# modem_breakout.net
KiCad netlist of a schematic drawn in EAGLE
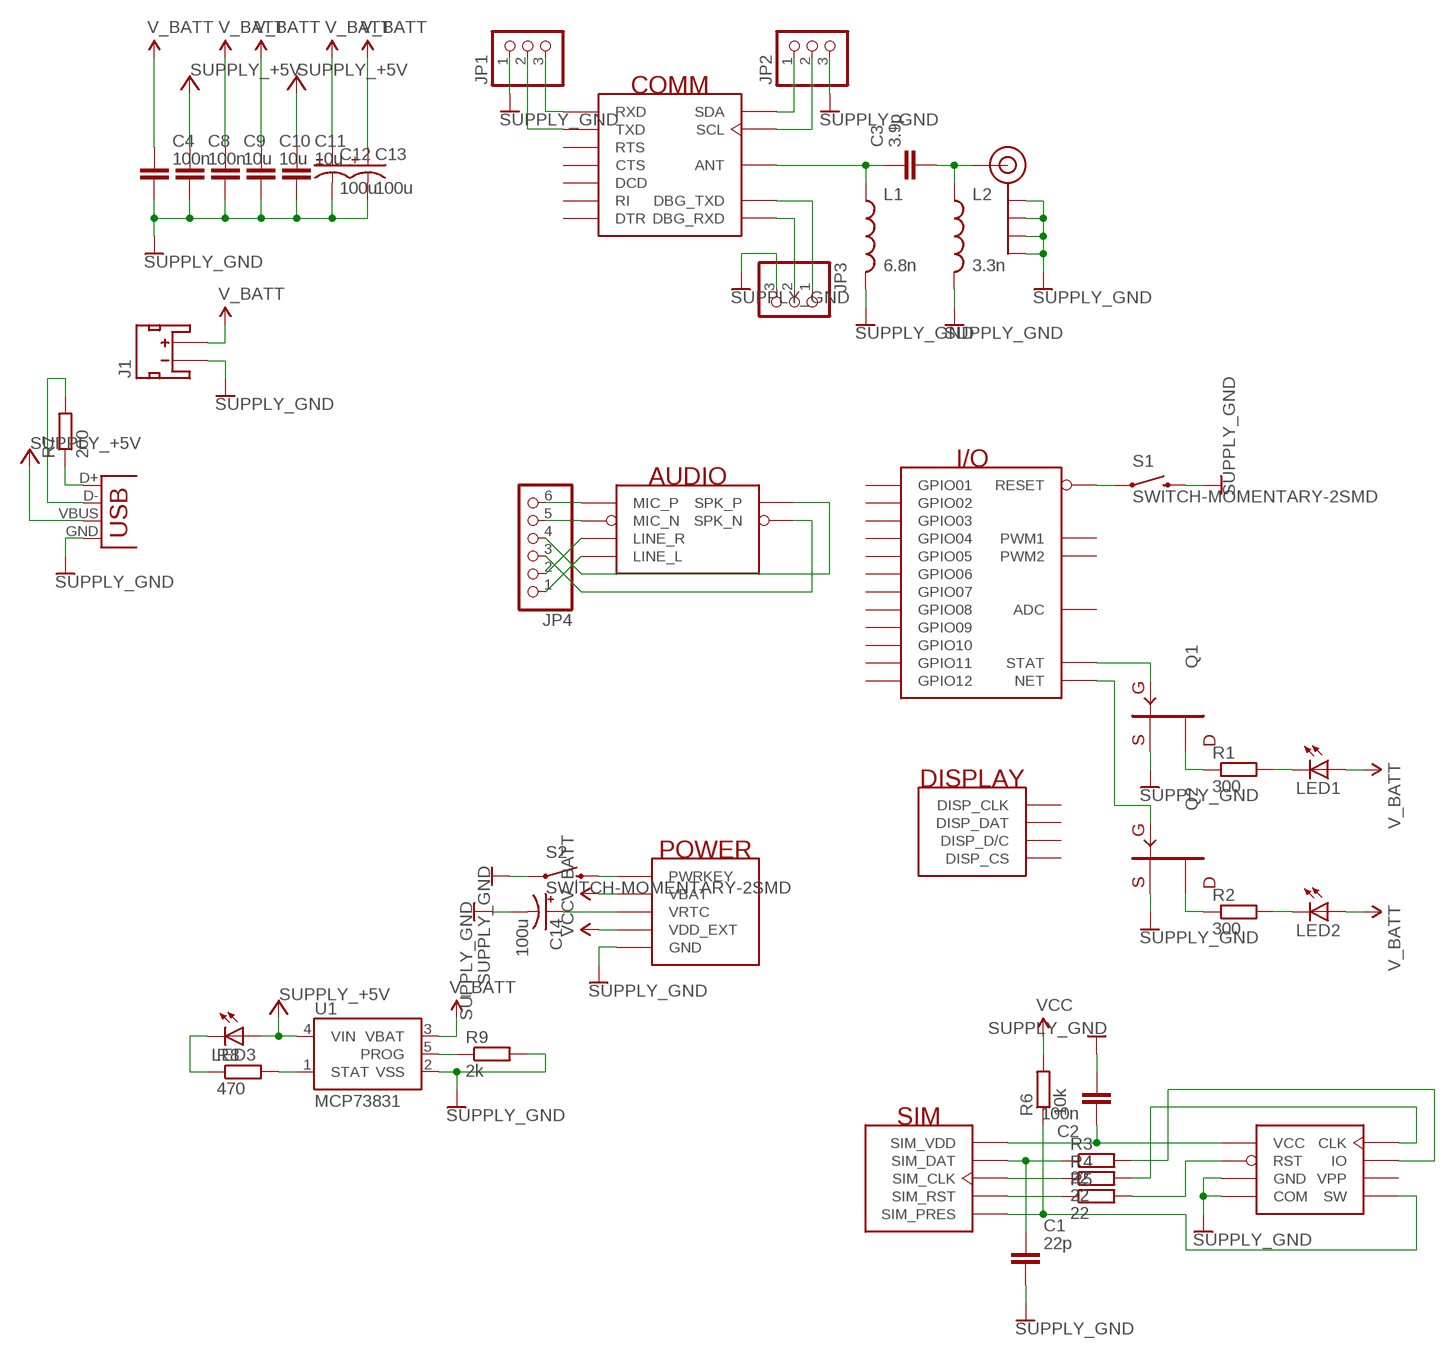
[diagram p0: schematic, sheet 1]

(export (version "E")
  (design (tool "Eeschema 10.0.6"))
  (components
    (comp (ref "C1")
      (value "22p")
      (footprint "eagle-import:C402")
      (libsource (lib "eagle-import") (part "CAPACITOR_NPOL-0402"))
    )
    (comp (ref "C2")
      (value "100n")
      (footprint "eagle-import:C402")
      (libsource (lib "eagle-import") (part "CAPACITOR_NPOL-0402"))
    )
    (comp (ref "C3")
      (value "3.9p")
      (footprint "eagle-import:C603")
      (libsource (lib "eagle-import") (part "CAPACITOR_NPOL-0603"))
    )
    (comp (ref "C4")
      (value "100n")
      (footprint "eagle-import:C402")
      (libsource (lib "eagle-import") (part "CAPACITOR_NPOL-0402"))
    )
    (comp (ref "C8")
      (value "100n")
      (footprint "eagle-import:C402")
      (libsource (lib "eagle-import") (part "CAPACITOR_NPOL-0402"))
    )
    (comp (ref "C9")
      (value "10u")
      (footprint "eagle-import:C805")
      (libsource (lib "eagle-import") (part "CAPACITOR_NPOL-0805"))
    )
    (comp (ref "C10")
      (value "10u")
      (footprint "eagle-import:C805")
      (libsource (lib "eagle-import") (part "CAPACITOR_NPOL-0805"))
    )
    (comp (ref "C11")
      (value "10u")
      (footprint "eagle-import:C805")
      (libsource (lib "eagle-import") (part "CAPACITOR_NPOL-0805"))
    )
    (comp (ref "C12")
      (value "100u")
      (footprint "eagle-import:EIA3528")
      (libsource (lib "eagle-import") (part "CAP_POL3528"))
    )
    (comp (ref "C13")
      (value "100u")
      (footprint "eagle-import:EIA3528")
      (libsource (lib "eagle-import") (part "CAP_POL3528"))
    )
    (comp (ref "C14")
      (value "100u")
      (footprint "eagle-import:EIA3528")
      (libsource (lib "eagle-import") (part "CAP_POL3528"))
    )
    (comp (ref "J$1")
      (value "SMA_EDGE")
      (footprint "eagle-import:SMA-EDGE")
      (libsource (lib "eagle-import") (part "SMA_EDGE"))
    )
    (comp (ref "J1")
      (value "JST_2MM_MALE")
      (footprint "eagle-import:JST-2-SMD")
      (libsource (lib "eagle-import") (part "JST_2MM_MALE"))
    )
    (comp (ref "JP1")
      (value "PINHD-1X3")
      (footprint "eagle-import:1X03")
      (libsource (lib "eagle-import") (part "PINHD-1X3"))
    )
    (comp (ref "JP2")
      (value "PINHD-1X3")
      (footprint "eagle-import:1X03")
      (libsource (lib "eagle-import") (part "PINHD-1X3"))
    )
    (comp (ref "JP3")
      (value "PINHD-1X3")
      (footprint "eagle-import:1X03")
      (libsource (lib "eagle-import") (part "PINHD-1X3"))
    )
    (comp (ref "JP4")
      (value "PINHD-1X6")
      (footprint "eagle-import:1X06")
      (libsource (lib "eagle-import") (part "PINHD-1X6"))
    )
    (comp (ref "JP5")
      (value "USB-SMD-NS")
      (footprint "eagle-import:USB-MINIB-NOSTOP")
      (libsource (lib "eagle-import") (part "USB-SMD-NS"))
    )
    (comp (ref "L1")
      (value "6.8n")
      (footprint "eagle-import:0603")
      (libsource (lib "eagle-import") (part "INDUCTOR0603"))
    )
    (comp (ref "L2")
      (value "3.3n")
      (footprint "eagle-import:0603")
      (libsource (lib "eagle-import") (part "INDUCTOR0603"))
    )
    (comp (ref "LED1")
      (value "LED-0603")
      (footprint "eagle-import:LED-603")
      (libsource (lib "eagle-import") (part "LED-0603"))
    )
    (comp (ref "LED2")
      (value "LED-0603")
      (footprint "eagle-import:LED-603")
      (libsource (lib "eagle-import") (part "LED-0603"))
    )
    (comp (ref "LED3")
      (value "LED-0603")
      (footprint "eagle-import:LED-603")
      (libsource (lib "eagle-import") (part "LED-0603"))
    )
    (comp (ref "Q1")
      (value "TRANSISTOR_FET-N")
      (footprint "eagle-import:SOT-23")
      (libsource (lib "eagle-import") (part "TRANSISTOR_FET-N"))
    )
    (comp (ref "Q2")
      (value "TRANSISTOR_FET-N")
      (footprint "eagle-import:SOT-23")
      (libsource (lib "eagle-import") (part "TRANSISTOR_FET-N"))
    )
    (comp (ref "R1")
      (value "300")
      (footprint "eagle-import:R603")
      (libsource (lib "eagle-import") (part "RESISTOR-0603"))
    )
    (comp (ref "R2")
      (value "300")
      (footprint "eagle-import:R603")
      (libsource (lib "eagle-import") (part "RESISTOR-0603"))
    )
    (comp (ref "R3")
      (value "22")
      (footprint "eagle-import:R402")
      (libsource (lib "eagle-import") (part "RESISTOR-0402"))
    )
    (comp (ref "R4")
      (value "22")
      (footprint "eagle-import:R402")
      (libsource (lib "eagle-import") (part "RESISTOR-0402"))
    )
    (comp (ref "R5")
      (value "22")
      (footprint "eagle-import:R402")
      (libsource (lib "eagle-import") (part "RESISTOR-0402"))
    )
    (comp (ref "R6")
      (value "10k")
      (footprint "eagle-import:R402")
      (libsource (lib "eagle-import") (part "RESISTOR-0402"))
    )
    (comp (ref "R7")
      (value "200")
      (footprint "eagle-import:R603")
      (libsource (lib "eagle-import") (part "RESISTOR-0603"))
    )
    (comp (ref "R8")
      (value "470")
      (footprint "eagle-import:R603")
      (libsource (lib "eagle-import") (part "RESISTOR-0603"))
    )
    (comp (ref "R9")
      (value "2k")
      (footprint "eagle-import:R402")
      (libsource (lib "eagle-import") (part "RESISTOR-0402"))
    )
    (comp (ref "S1")
      (value "SWITCH-MOMENTARY-2SMD")
      (footprint "eagle-import:TACTILE_SWITCH_SMD")
      (libsource (lib "eagle-import") (part "SWITCH-MOMENTARY-2SMD"))
    )
    (comp (ref "S2")
      (value "SWITCH-MOMENTARY-2SMD")
      (footprint "eagle-import:TACTILE_SWITCH_SMD")
      (libsource (lib "eagle-import") (part "SWITCH-MOMENTARY-2SMD"))
    )
    (comp (ref "U$1")
      (value "SIM900")
      (footprint "eagle-import:SIM900")
      (libsource (lib "eagle-import") (part "SIM900"))
    )
    (comp (ref "U$2")
      (value "SIM-MICRO")
      (footprint "eagle-import:1041180811")
      (libsource (lib "eagle-import") (part "SIM-MICRO"))
    )
    (comp (ref "U1")
      (value "MCP73831")
      (footprint "eagle-import:SOT23-5")
      (libsource (lib "eagle-import") (part "MCP73831"))
    )
  )
  (nets
    (net (code "1") (name "Net-(C14-+)") (class "Default")
      (node (ref "C14") (pin "A") (pinfunction "+_A") (pintype "passive"))
      (node (ref "U$1") (pin "P$26") (pinfunction "VRTC_P$26") (pintype "power_in"))
    )
    (net (code "2") (name "Net-(J$1-SIGNAL)") (class "Default")
      (node (ref "C3") (pin "2") (pinfunction "2_2") (pintype "passive"))
      (node (ref "J$1") (pin "SIG") (pinfunction "SIGNAL_SIG") (pintype "bidirectional"))
      (node (ref "L2") (pin "1") (pinfunction "1_1") (pintype "passive"))
    )
    (net (code "3") (name "Net-(JP5-PadD+)") (class "Default")
      (node (ref "JP5") (pin "D+") (pinfunction "D+_D+") (pintype "bidirectional"))
      (node (ref "R7") (pin "1") (pinfunction "1_1") (pintype "passive"))
    )
    (net (code "4") (name "Net-(JP5-PadD-)") (class "Default")
      (node (ref "JP5") (pin "D-") (pinfunction "D-_D-") (pintype "bidirectional"))
      (node (ref "R7") (pin "2") (pinfunction "2_2") (pintype "passive"))
    )
    (net (code "5") (name "Net-(LED1-PadC)") (class "Default")
      (node (ref "LED1") (pin "C") (pinfunction "C_C") (pintype "passive"))
      (node (ref "R1") (pin "2") (pinfunction "2_2") (pintype "passive"))
    )
    (net (code "6") (name "Net-(LED2-PadC)") (class "Default")
      (node (ref "LED2") (pin "C") (pinfunction "C_C") (pintype "passive"))
      (node (ref "R2") (pin "2") (pinfunction "2_2") (pintype "passive"))
    )
    (net (code "7") (name "Net-(LED3-PadC)") (class "Default")
      (node (ref "LED3") (pin "C") (pinfunction "C_C") (pintype "passive"))
      (node (ref "R8") (pin "1") (pinfunction "1_1") (pintype "passive"))
    )
    (net (code "8") (name "Net-(Q1-D)") (class "Default")
      (node (ref "Q1") (pin "3") (pinfunction "D_3") (pintype "bidirectional"))
      (node (ref "R1") (pin "1") (pinfunction "1_1") (pintype "passive"))
    )
    (net (code "9") (name "Net-(Q1-G)") (class "Default")
      (node (ref "Q1") (pin "1") (pinfunction "G_1") (pintype "bidirectional"))
      (node (ref "U$1") (pin "P$66") (pinfunction "STAT_P$66") (pintype "output"))
    )
    (net (code "10") (name "Net-(Q2-D)") (class "Default")
      (node (ref "Q2") (pin "3") (pinfunction "D_3") (pintype "bidirectional"))
      (node (ref "R2") (pin "1") (pinfunction "1_1") (pintype "passive"))
    )
    (net (code "11") (name "Net-(Q2-G)") (class "Default")
      (node (ref "Q2") (pin "1") (pinfunction "G_1") (pintype "bidirectional"))
      (node (ref "U$1") (pin "P$52") (pinfunction "NET_P$52") (pintype "output"))
    )
    (net (code "12") (name "Net-(S2-2)") (class "Default")
      (node (ref "S2") (pin "3") (pinfunction "2_3") (pintype "passive"))
      (node (ref "U$1") (pin "P$1") (pinfunction "PWRKEY_P$1") (pintype "input"))
    )
    (net (code "13") (name "Net-(U$1A-LINE_L)") (class "Default")
      (node (ref "JP4") (pin "1") (pinfunction "1_1") (pintype "passive"))
      (node (ref "U$1") (pin "P$24") (pinfunction "LINE_L_P$24") (pintype "input"))
    )
    (net (code "14") (name "Net-(U$1A-LINE_R)") (class "Default")
      (node (ref "JP4") (pin "2") (pinfunction "2_2") (pintype "passive"))
      (node (ref "U$1") (pin "P$23") (pinfunction "LINE_R_P$23") (pintype "input"))
    )
    (net (code "15") (name "Net-(U$1A-MIC_N)") (class "Default")
      (node (ref "JP4") (pin "5") (pinfunction "5_5") (pintype "passive"))
      (node (ref "U$1") (pin "P$20") (pinfunction "MIC_N_P$20") (pintype "input"))
    )
    (net (code "16") (name "Net-(U$1A-MIC_P)") (class "Default")
      (node (ref "JP4") (pin "6") (pinfunction "6_6") (pintype "passive"))
      (node (ref "U$1") (pin "P$19") (pinfunction "MIC_P_P$19") (pintype "input"))
    )
    (net (code "17") (name "Net-(U$1A-SPK_N)") (class "Default")
      (node (ref "JP4") (pin "3") (pinfunction "3_3") (pintype "passive"))
      (node (ref "U$1") (pin "P$22") (pinfunction "SPK_N_P$22") (pintype "output"))
    )
    (net (code "18") (name "Net-(U$1A-SPK_P)") (class "Default")
      (node (ref "JP4") (pin "4") (pinfunction "4_4") (pintype "passive"))
      (node (ref "U$1") (pin "P$21") (pinfunction "SPK_P_P$21") (pintype "output"))
    )
    (net (code "19") (name "Net-(U$1B-ANT)") (class "Default")
      (node (ref "C3") (pin "1") (pinfunction "1_1") (pintype "passive"))
      (node (ref "L1") (pin "1") (pinfunction "1_1") (pintype "passive"))
      (node (ref "U$1") (pin "P$60") (pinfunction "ANT_P$60") (pintype "bidirectional"))
    )
    (net (code "20") (name "Net-(U$1B-DBG_RXD)") (class "Default")
      (node (ref "JP3") (pin "2") (pinfunction "2_2") (pintype "passive"))
      (node (ref "U$1") (pin "P$28") (pinfunction "DBG_RXD_P$28") (pintype "input"))
    )
    (net (code "21") (name "Net-(U$1B-DBG_TXD)") (class "Default")
      (node (ref "JP3") (pin "1") (pinfunction "1_1") (pintype "passive"))
      (node (ref "U$1") (pin "P$27") (pinfunction "DBG_TXD_P$27") (pintype "output"))
    )
    (net (code "22") (name "Net-(U$1B-RXD)") (class "Default")
      (node (ref "JP1") (pin "3") (pinfunction "3_3") (pintype "passive"))
      (node (ref "U$1") (pin "P$10") (pinfunction "RXD_P$10") (pintype "input"))
    )
    (net (code "23") (name "Net-(U$1B-SCL)") (class "Default")
      (node (ref "JP2") (pin "2") (pinfunction "2_2") (pintype "passive"))
      (node (ref "U$1") (pin "P$38") (pinfunction "SCL_P$38") (pintype "bidirectional"))
    )
    (net (code "24") (name "Net-(U$1B-SDA)") (class "Default")
      (node (ref "JP2") (pin "1") (pinfunction "1_1") (pintype "passive"))
      (node (ref "U$1") (pin "P$37") (pinfunction "SDA_P$37") (pintype "output"))
    )
    (net (code "25") (name "Net-(U$1B-TXD)") (class "Default")
      (node (ref "JP1") (pin "2") (pinfunction "2_2") (pintype "passive"))
      (node (ref "U$1") (pin "P$9") (pinfunction "TXD_P$9") (pintype "output"))
    )
    (net (code "26") (name "Net-(U$1C-RESET)") (class "Default")
      (node (ref "S1") (pin "1") (pinfunction "1_1") (pintype "passive"))
      (node (ref "U$1") (pin "P$16") (pinfunction "RESET_P$16") (pintype "input"))
    )
    (net (code "27") (name "Net-(U$1F-SIM_CLK)") (class "Default")
      (node (ref "R4") (pin "1") (pinfunction "1_1") (pintype "passive"))
      (node (ref "U$1") (pin "P$32") (pinfunction "SIM_CLK_P$32") (pintype "output"))
    )
    (net (code "28") (name "Net-(U$1F-SIM_DAT)") (class "Default")
      (node (ref "C1") (pin "1") (pinfunction "1_1") (pintype "passive"))
      (node (ref "R3") (pin "1") (pinfunction "1_1") (pintype "passive"))
      (node (ref "U$1") (pin "P$31") (pinfunction "SIM_DAT_P$31") (pintype "bidirectional"))
    )
    (net (code "29") (name "Net-(U$1F-SIM_PRES)") (class "Default")
      (node (ref "R6") (pin "1") (pinfunction "1_1") (pintype "passive"))
      (node (ref "U$1") (pin "P$34") (pinfunction "SIM_PRES_P$34") (pintype "input"))
      (node (ref "U$2") (pin "DETECT") (pinfunction "SW_DETECT") (pintype "bidirectional"))
    )
    (net (code "30") (name "Net-(U$1F-SIM_RST)") (class "Default")
      (node (ref "R5") (pin "1") (pinfunction "1_1") (pintype "passive"))
      (node (ref "U$1") (pin "P$33") (pinfunction "SIM_RST_P$33") (pintype "output"))
    )
    (net (code "31") (name "Net-(U$1F-SIM_VDD)") (class "Default")
      (node (ref "C2") (pin "1") (pinfunction "1_1") (pintype "passive"))
      (node (ref "U$1") (pin "P$30") (pinfunction "SIM_VDD_P$30") (pintype "power_in"))
      (node (ref "U$2") (pin "1") (pinfunction "VCC_1") (pintype "power_in"))
    )
    (net (code "32") (name "Net-(U$2-CLK)") (class "Default")
      (node (ref "R4") (pin "2") (pinfunction "2_2") (pintype "passive"))
      (node (ref "U$2") (pin "3") (pinfunction "CLK_3") (pintype "input"))
    )
    (net (code "33") (name "Net-(U$2-IO)") (class "Default")
      (node (ref "R3") (pin "2") (pinfunction "2_2") (pintype "passive"))
      (node (ref "U$2") (pin "7") (pinfunction "IO_7") (pintype "bidirectional"))
    )
    (net (code "34") (name "Net-(U$2-RST)") (class "Default")
      (node (ref "R5") (pin "2") (pinfunction "2_2") (pintype "passive"))
      (node (ref "U$2") (pin "2") (pinfunction "RST_2") (pintype "input"))
    )
    (net (code "35") (name "Net-(U1-PROG)") (class "Default")
      (node (ref "R9") (pin "1") (pinfunction "1_1") (pintype "passive"))
      (node (ref "U1") (pin "5") (pinfunction "PROG_5") (pintype "input"))
    )
    (net (code "36") (name "Net-(U1-STAT)") (class "Default")
      (node (ref "R8") (pin "2") (pinfunction "2_2") (pintype "passive"))
      (node (ref "U1") (pin "1") (pinfunction "STAT_1") (pintype "output"))
    )
    (net (code "37") (name "SUPPLY_+5V") (class "Default")
      (node (ref "C11") (pin "1") (pinfunction "1_1") (pintype "passive"))
      (node (ref "C8") (pin "1") (pinfunction "1_1") (pintype "passive"))
      (node (ref "JP5") (pin "VBUS") (pinfunction "VBUS_VBUS") (pintype "bidirectional"))
      (node (ref "LED3") (pin "A") (pinfunction "A_A") (pintype "passive"))
      (node (ref "U1") (pin "4") (pinfunction "VIN_4") (pintype "power_in"))
    )
    (net (code "38") (name "SUPPLY_GND") (class "Default")
      (node (ref "C1") (pin "2") (pinfunction "2_2") (pintype "passive"))
      (node (ref "C10") (pin "2") (pinfunction "2_2") (pintype "passive"))
      (node (ref "C11") (pin "2") (pinfunction "2_2") (pintype "passive"))
      (node (ref "C12") (pin "C") (pinfunction "-_C") (pintype "passive"))
      (node (ref "C13") (pin "C") (pinfunction "-_C") (pintype "passive"))
      (node (ref "C14") (pin "C") (pinfunction "-_C") (pintype "passive"))
      (node (ref "C2") (pin "2") (pinfunction "2_2") (pintype "passive"))
      (node (ref "C4") (pin "2") (pinfunction "2_2") (pintype "passive"))
      (node (ref "C8") (pin "2") (pinfunction "2_2") (pintype "passive"))
      (node (ref "C9") (pin "2") (pinfunction "2_2") (pintype "passive"))
      (node (ref "J$1") (pin "GND@0") (pinfunction "GND_GND@0") (pintype "bidirectional"))
      (node (ref "J$1") (pin "GND@1") (pinfunction "GND_GND@1") (pintype "bidirectional"))
      (node (ref "J$1") (pin "GND@2") (pinfunction "GND_GND@2") (pintype "bidirectional"))
      (node (ref "J$1") (pin "GND@3") (pinfunction "GND_GND@3") (pintype "bidirectional"))
      (node (ref "J1") (pin "1") (pinfunction "-_1") (pintype "bidirectional"))
      (node (ref "JP1") (pin "1") (pinfunction "1_1") (pintype "passive"))
      (node (ref "JP2") (pin "3") (pinfunction "3_3") (pintype "passive"))
      (node (ref "JP3") (pin "3") (pinfunction "3_3") (pintype "passive"))
      (node (ref "JP5") (pin "GND") (pinfunction "GND_GND") (pintype "bidirectional"))
      (node (ref "L1") (pin "2") (pinfunction "2_2") (pintype "passive"))
      (node (ref "L2") (pin "2") (pinfunction "2_2") (pintype "passive"))
      (node (ref "Q1") (pin "2") (pinfunction "S_2") (pintype "bidirectional"))
      (node (ref "Q2") (pin "2") (pinfunction "S_2") (pintype "bidirectional"))
      (node (ref "R9") (pin "2") (pinfunction "2_2") (pintype "passive"))
      (node (ref "S1") (pin "3") (pinfunction "2_3") (pintype "passive"))
      (node (ref "S2") (pin "1") (pinfunction "1_1") (pintype "passive"))
      (node (ref "U$1") (pin "P$17") (pinfunction "GND_P$17") (pintype "power_in"))
      (node (ref "U$1") (pin "P$18") (pinfunction "GND_P$18") (pintype "power_in"))
      (node (ref "U$1") (pin "P$29") (pinfunction "GND_P$29") (pintype "power_in"))
      (node (ref "U$1") (pin "P$39") (pinfunction "GND_P$39") (pintype "power_in"))
      (node (ref "U$1") (pin "P$45") (pinfunction "GND_P$45") (pintype "power_in"))
      (node (ref "U$1") (pin "P$46") (pinfunction "GND_P$46") (pintype "power_in"))
      (node (ref "U$1") (pin "P$53") (pinfunction "GND_P$53") (pintype "power_in"))
      (node (ref "U$1") (pin "P$54") (pinfunction "GND_P$54") (pintype "power_in"))
      (node (ref "U$1") (pin "P$58") (pinfunction "GND_P$58") (pintype "power_in"))
      (node (ref "U$1") (pin "P$59") (pinfunction "GND_P$59") (pintype "power_in"))
      (node (ref "U$1") (pin "P$61") (pinfunction "GND_P$61") (pintype "power_in"))
      (node (ref "U$1") (pin "P$62") (pinfunction "GND_P$62") (pintype "power_in"))
      (node (ref "U$1") (pin "P$63") (pinfunction "GND_P$63") (pintype "power_in"))
      (node (ref "U$1") (pin "P$64") (pinfunction "GND_P$64") (pintype "power_in"))
      (node (ref "U$1") (pin "P$65") (pinfunction "GND_P$65") (pintype "power_in"))
      (node (ref "U$2") (pin "5") (pinfunction "GND_5") (pintype "power_in"))
      (node (ref "U$2") (pin "COMMON") (pinfunction "COM_COMMON") (pintype "bidirectional"))
      (node (ref "U$2") (pin "G1") (pinfunction "GND_G1") (pintype "power_in"))
      (node (ref "U$2") (pin "G2") (pinfunction "GND_G2") (pintype "power_in"))
      (node (ref "U$2") (pin "G3") (pinfunction "GND_G3") (pintype "power_in"))
      (node (ref "U$2") (pin "G4") (pinfunction "GND_G4") (pintype "power_in"))
      (node (ref "U$2") (pin "G5") (pinfunction "GND_G5") (pintype "power_in"))
      (node (ref "U$2") (pin "G6") (pinfunction "GND_G6") (pintype "power_in"))
      (node (ref "U1") (pin "2") (pinfunction "VSS_2") (pintype "power_in"))
    )
    (net (code "39") (name "VCC") (class "Default")
      (node (ref "R6") (pin "2") (pinfunction "2_2") (pintype "passive"))
      (node (ref "U$1") (pin "P$15") (pinfunction "VDD_EXT_P$15") (pintype "power_in"))
    )
    (net (code "40") (name "V_BATT") (class "Default")
      (node (ref "C10") (pin "1") (pinfunction "1_1") (pintype "passive"))
      (node (ref "C12") (pin "A") (pinfunction "+_A") (pintype "passive"))
      (node (ref "C13") (pin "A") (pinfunction "+_A") (pintype "passive"))
      (node (ref "C4") (pin "1") (pinfunction "1_1") (pintype "passive"))
      (node (ref "C9") (pin "1") (pinfunction "1_1") (pintype "passive"))
      (node (ref "J1") (pin "2") (pinfunction "+_2") (pintype "bidirectional"))
      (node (ref "LED1") (pin "A") (pinfunction "A_A") (pintype "passive"))
      (node (ref "LED2") (pin "A") (pinfunction "A_A") (pintype "passive"))
      (node (ref "U$1") (pin "P$55") (pinfunction "VBAT_P$55") (pintype "power_in"))
      (node (ref "U$1") (pin "P$56") (pinfunction "VBAT_P$56") (pintype "power_in"))
      (node (ref "U$1") (pin "P$57") (pinfunction "VBAT_P$57") (pintype "power_in"))
      (node (ref "U1") (pin "3") (pinfunction "VBAT_3") (pintype "power_in"))
    )
    (net (code "41") (name "unconnected-(J1-PAD1-PadNC1)") (class "Default")
      (node (ref "J1") (pin "NC1") (pinfunction "PAD1_NC1") (pintype "bidirectional"))
    )
    (net (code "42") (name "unconnected-(J1-PAD2-PadNC2)") (class "Default")
      (node (ref "J1") (pin "NC2") (pinfunction "PAD2_NC2") (pintype "bidirectional"))
    )
    (net (code "43") (name "unconnected-(U$1B-CTS-PadP$7)") (class "Default")
      (node (ref "U$1") (pin "P$7") (pinfunction "CTS_P$7") (pintype "output"))
    )
    (net (code "44") (name "unconnected-(U$1B-DCD-PadP$5)") (class "Default")
      (node (ref "U$1") (pin "P$5") (pinfunction "DCD_P$5") (pintype "output"))
    )
    (net (code "45") (name "unconnected-(U$1B-DTR-PadP$3)") (class "Default")
      (node (ref "U$1") (pin "P$3") (pinfunction "DTR_P$3") (pintype "input"))
    )
    (net (code "46") (name "unconnected-(U$1B-RI-PadP$4)") (class "Default")
      (node (ref "U$1") (pin "P$4") (pinfunction "RI_P$4") (pintype "output"))
    )
    (net (code "47") (name "unconnected-(U$1B-RTS-PadP$8)") (class "Default")
      (node (ref "U$1") (pin "P$8") (pinfunction "RTS_P$8") (pintype "input"))
    )
    (net (code "48") (name "unconnected-(U$1C-ADC-PadP$25)") (class "Default")
      (node (ref "U$1") (pin "P$25") (pinfunction "ADC_P$25") (pintype "input"))
    )
    (net (code "49") (name "unconnected-(U$1C-GPIO01-PadP$40)") (class "Default")
      (node (ref "U$1") (pin "P$40") (pinfunction "GPIO01_P$40") (pintype "bidirectional"))
    )
    (net (code "50") (name "unconnected-(U$1C-GPIO02-PadP$41)") (class "Default")
      (node (ref "U$1") (pin "P$41") (pinfunction "GPIO02_P$41") (pintype "bidirectional"))
    )
    (net (code "51") (name "unconnected-(U$1C-GPIO03-PadP$42)") (class "Default")
      (node (ref "U$1") (pin "P$42") (pinfunction "GPIO03_P$42") (pintype "bidirectional"))
    )
    (net (code "52") (name "unconnected-(U$1C-GPIO04-PadP$43)") (class "Default")
      (node (ref "U$1") (pin "P$43") (pinfunction "GPIO04_P$43") (pintype "bidirectional"))
    )
    (net (code "53") (name "unconnected-(U$1C-GPIO05-PadP$44)") (class "Default")
      (node (ref "U$1") (pin "P$44") (pinfunction "GPIO05_P$44") (pintype "bidirectional"))
    )
    (net (code "54") (name "unconnected-(U$1C-GPIO06-PadP$47)") (class "Default")
      (node (ref "U$1") (pin "P$47") (pinfunction "GPIO06_P$47") (pintype "bidirectional"))
    )
    (net (code "55") (name "unconnected-(U$1C-GPIO07-PadP$48)") (class "Default")
      (node (ref "U$1") (pin "P$48") (pinfunction "GPIO07_P$48") (pintype "bidirectional"))
    )
    (net (code "56") (name "unconnected-(U$1C-GPIO08-PadP$49)") (class "Default")
      (node (ref "U$1") (pin "P$49") (pinfunction "GPIO08_P$49") (pintype "bidirectional"))
    )
    (net (code "57") (name "unconnected-(U$1C-GPIO09-PadP$50)") (class "Default")
      (node (ref "U$1") (pin "P$50") (pinfunction "GPIO09_P$50") (pintype "bidirectional"))
    )
    (net (code "58") (name "unconnected-(U$1C-GPIO10-PadP$51)") (class "Default")
      (node (ref "U$1") (pin "P$51") (pinfunction "GPIO10_P$51") (pintype "bidirectional"))
    )
    (net (code "59") (name "unconnected-(U$1C-GPIO11-PadP$67)") (class "Default")
      (node (ref "U$1") (pin "P$67") (pinfunction "GPIO11_P$67") (pintype "bidirectional"))
    )
    (net (code "60") (name "unconnected-(U$1C-GPIO12-PadP$68)") (class "Default")
      (node (ref "U$1") (pin "P$68") (pinfunction "GPIO12_P$68") (pintype "bidirectional"))
    )
    (net (code "61") (name "unconnected-(U$1C-PWM1-PadP$35)") (class "Default")
      (node (ref "U$1") (pin "P$35") (pinfunction "PWM1_P$35") (pintype "output"))
    )
    (net (code "62") (name "unconnected-(U$1C-PWM2-PadP$36)") (class "Default")
      (node (ref "U$1") (pin "P$36") (pinfunction "PWM2_P$36") (pintype "output"))
    )
    (net (code "63") (name "unconnected-(U$1D-DISP_CLK-PadP$11)") (class "Default")
      (node (ref "U$1") (pin "P$11") (pinfunction "DISP_CLK_P$11") (pintype "output"))
    )
    (net (code "64") (name "unconnected-(U$1D-DISP_CS-PadP$14)") (class "Default")
      (node (ref "U$1") (pin "P$14") (pinfunction "DISP_CS_P$14") (pintype "output"))
    )
    (net (code "65") (name "unconnected-(U$1D-DISP_DAT-PadP$12)") (class "Default")
      (node (ref "U$1") (pin "P$12") (pinfunction "DISP_DAT_P$12") (pintype "bidirectional"))
    )
    (net (code "66") (name "unconnected-(U$1D-DISP_D{slash}C-PadP$13)") (class "Default")
      (node (ref "U$1") (pin "P$13") (pinfunction "DISP_D/C_P$13") (pintype "output"))
    )
    (net (code "67") (name "unconnected-(U$2-VPP-Pad6)") (class "Default")
      (node (ref "U$2") (pin "6") (pinfunction "VPP_6") (pintype "bidirectional"))
    )
  )
)
